# Sheet2.net
KiCad netlist of a schematic drawn in Altium Designer
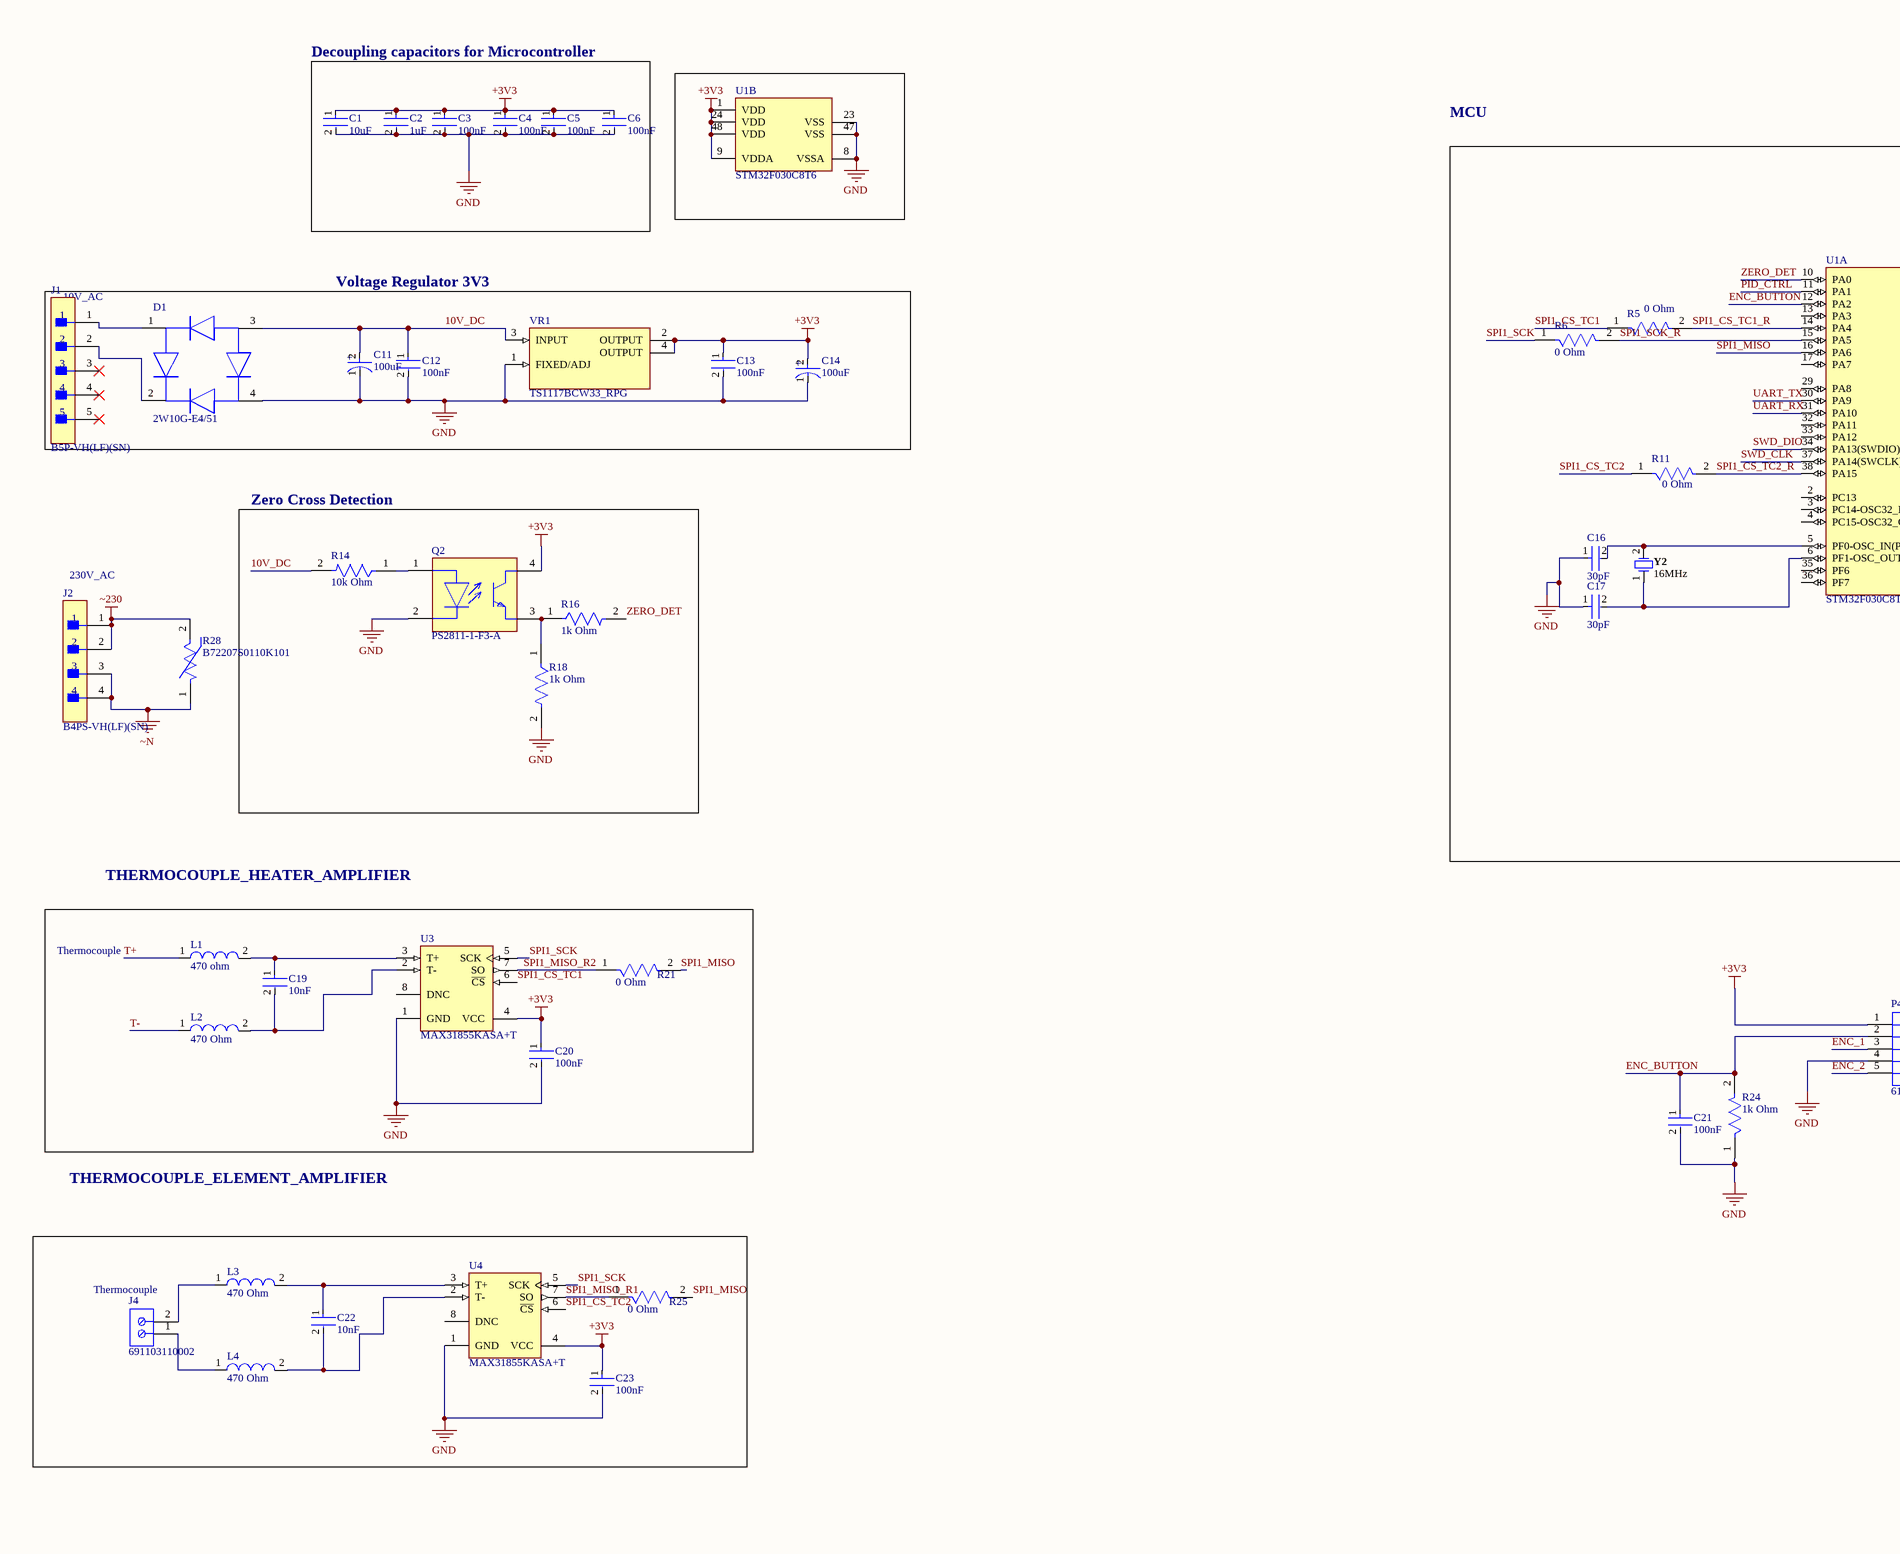
[diagram p0: Sheet2.SchDoc, left]
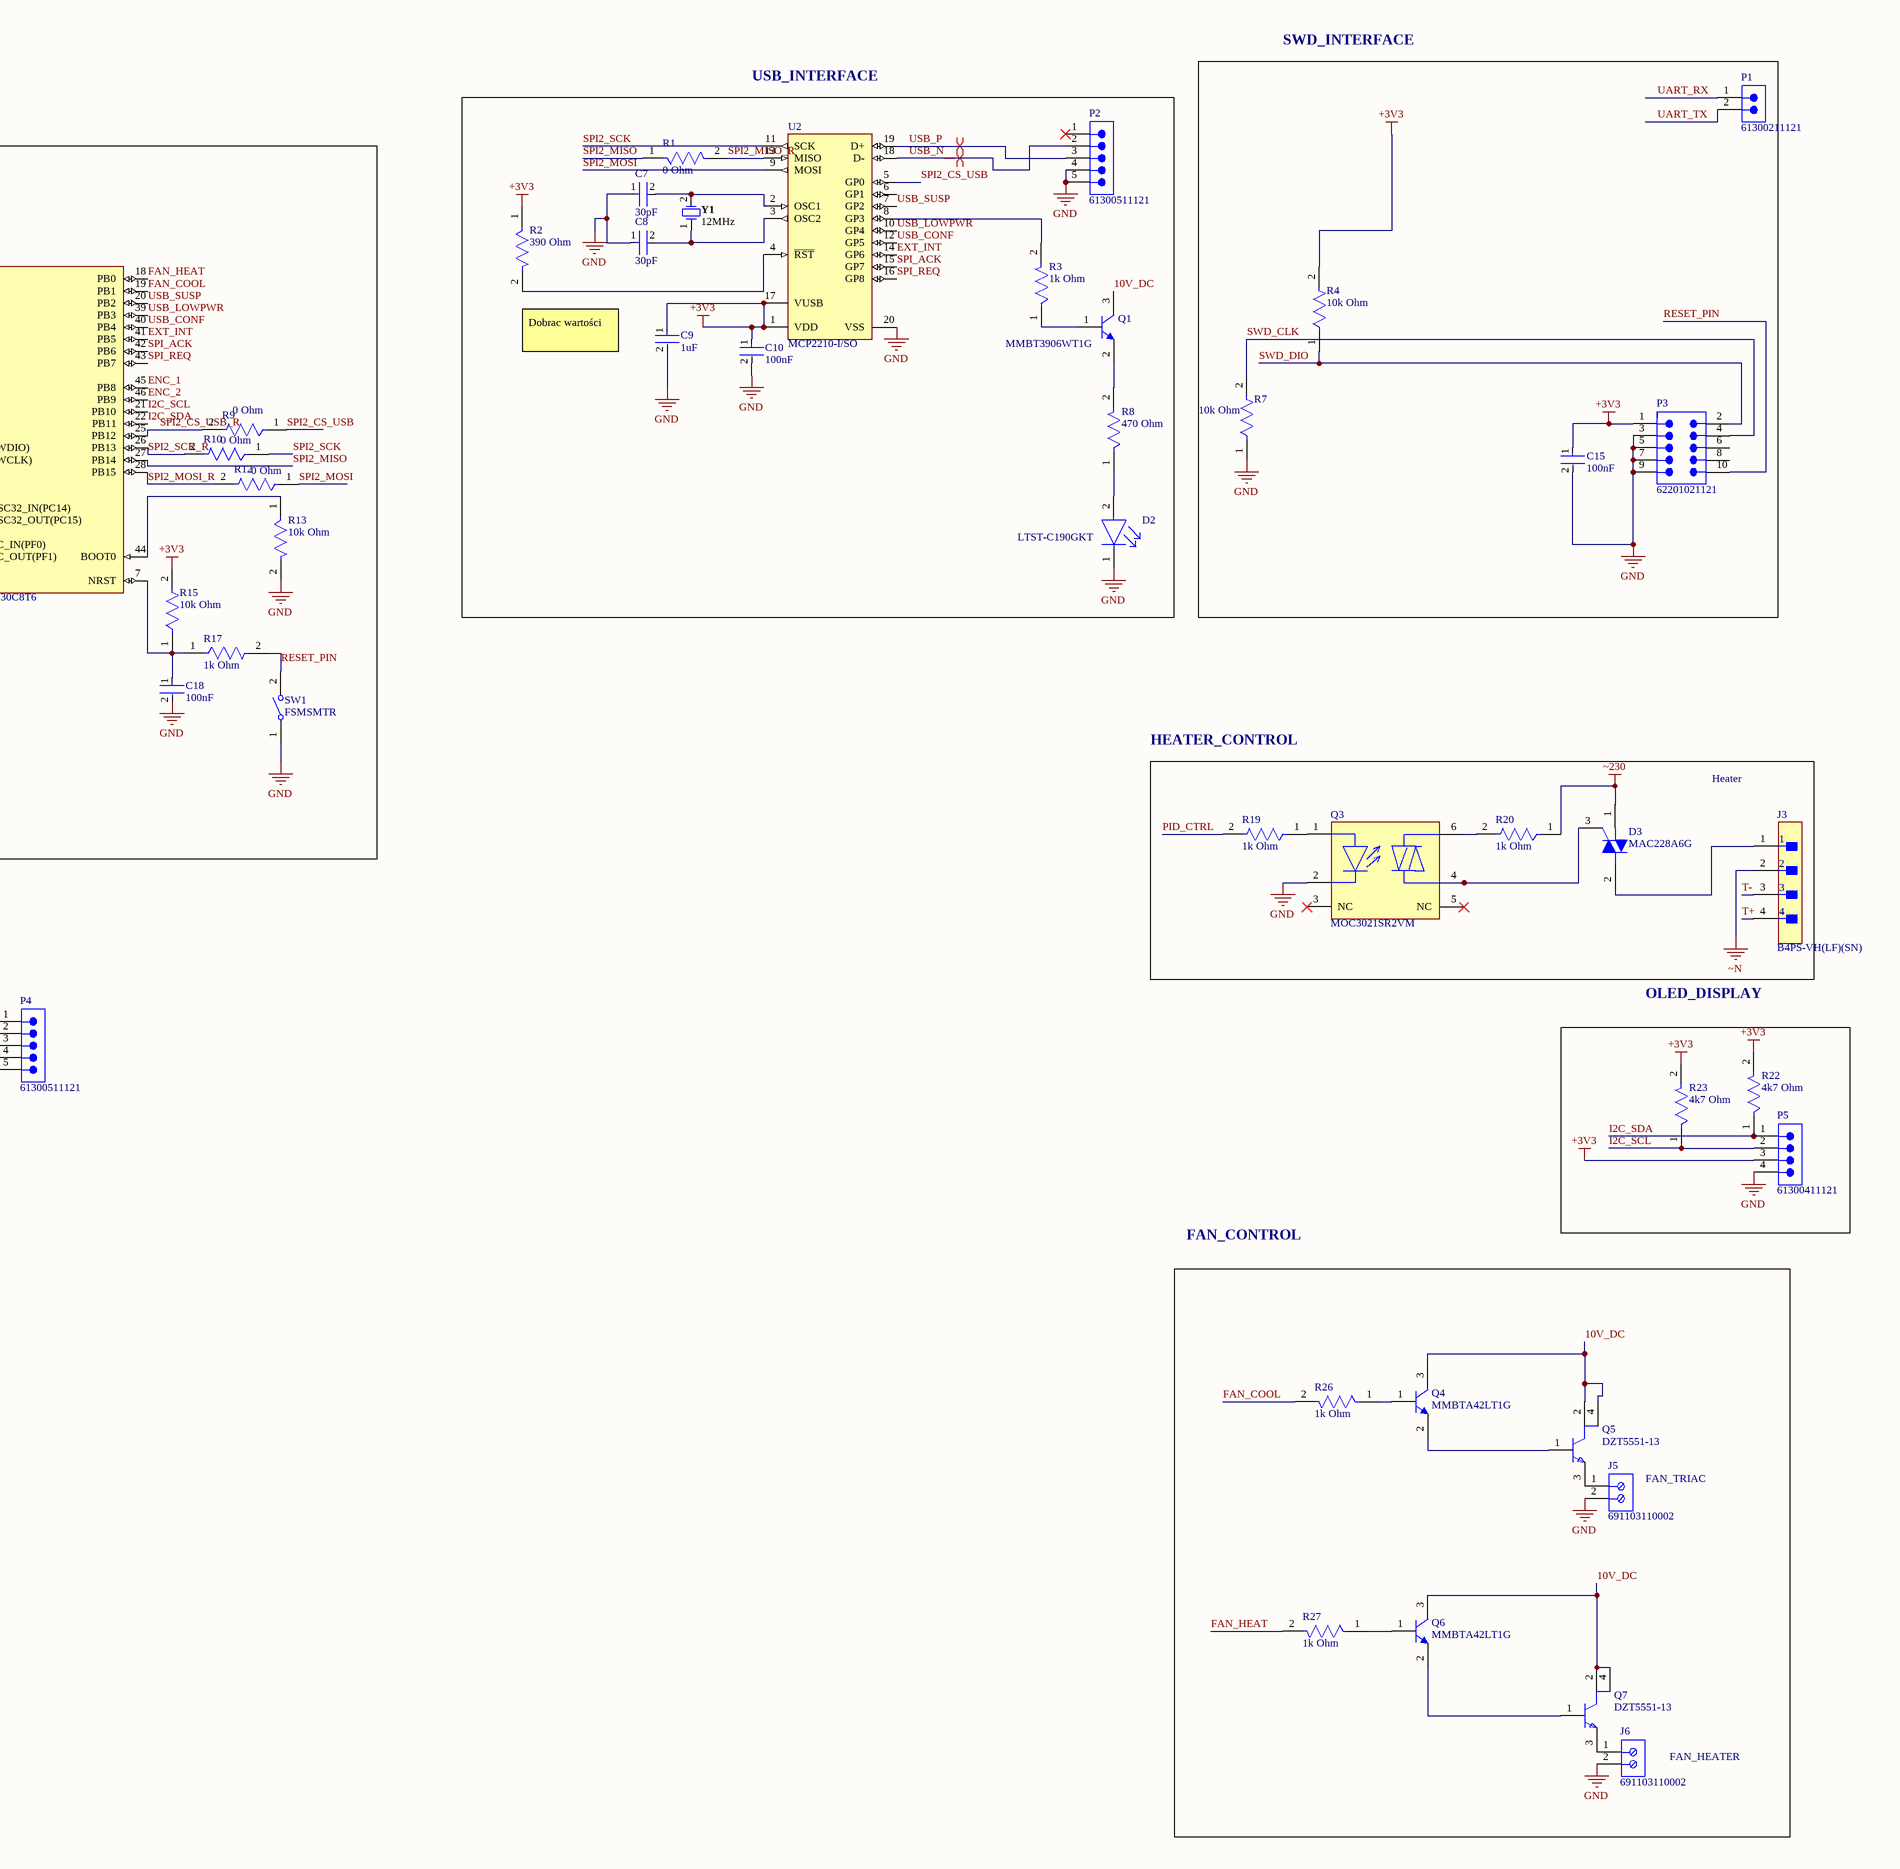
[diagram p1: Sheet2.SchDoc, right]

(export (version "E")
  (design (tool "Eeschema 10.0.6"))
  (components
    (comp (ref "C1")
      (value "10uF")
      (footprint "FP-CC0805-0_85-MFG")
      (description "CAP CER 0.1UF 50V X7R 0805")
      (fields (field (name "TOLERANCE") "0.1") (field (name "MANUFACTURER PART NUMBER") "CC0805KRX7R9BB104"))
      (libsource (lib "Altium Content Vault") (part "11868f565c42a9108669ba33697ecf6"))
    )
    (comp (ref "C2")
      (value "1uF")
      (footprint "FP-CC0805-0_85-MFG")
      (description "CAP CER 0.1UF 50V X7R 0805")
      (fields (field (name "TOLERANCE") "0.1") (field (name "MANUFACTURER PART NUMBER") "CC0805KRX7R9BB104"))
      (libsource (lib "Altium Content Vault") (part "11868f565c42a9108669ba33697ecf6"))
    )
    (comp (ref "C3")
      (value "100nF")
      (footprint "FP-CC0805-0_85-MFG")
      (description "CAP CER 0.1UF 50V X7R 0805")
      (fields (field (name "TOLERANCE") "0.1") (field (name "MANUFACTURER PART NUMBER") "CC0805KRX7R9BB104"))
      (libsource (lib "Altium Content Vault") (part "11868f565c42a9108669ba33697ecf6"))
    )
    (comp (ref "C4")
      (value "100nF")
      (footprint "FP-CC0805-0_85-MFG")
      (description "CAP CER 0.1UF 50V X7R 0805")
      (fields (field (name "TOLERANCE") "0.1") (field (name "MANUFACTURER PART NUMBER") "CC0805KRX7R9BB104"))
      (libsource (lib "Altium Content Vault") (part "11868f565c42a9108669ba33697ecf6"))
    )
    (comp (ref "C5")
      (value "100nF")
      (footprint "FP-CC0805-0_85-MFG")
      (description "CAP CER 0.1UF 50V X7R 0805")
      (fields (field (name "TOLERANCE") "0.1") (field (name "MANUFACTURER PART NUMBER") "CC0805KRX7R9BB104"))
      (libsource (lib "Altium Content Vault") (part "11868f565c42a9108669ba33697ecf6"))
    )
    (comp (ref "C6")
      (value "100nF")
      (footprint "FP-CC0805-0_85-MFG")
      (description "CAP CER 0.1UF 50V X7R 0805")
      (fields (field (name "TOLERANCE") "0.1") (field (name "MANUFACTURER PART NUMBER") "CC0805KRX7R9BB104"))
      (libsource (lib "Altium Content Vault") (part "11868f565c42a9108669ba33697ecf6"))
    )
    (comp (ref "C7")
      (value "30pF")
      (footprint "FP-CC0805-0_85-MFG")
      (description "CAP CER 0.1UF 50V X7R 0805")
      (fields (field (name "TOLERANCE") "0.1") (field (name "MANUFACTURER PART NUMBER") "CC0805KRX7R9BB104"))
      (libsource (lib "Altium Content Vault") (part "11868f565c42a9108669ba33697ecf6"))
    )
    (comp (ref "C8")
      (value "30pF")
      (footprint "FP-CC0805-0_85-MFG")
      (description "CAP CER 0.1UF 50V X7R 0805")
      (fields (field (name "TOLERANCE") "0.1") (field (name "MANUFACTURER PART NUMBER") "CC0805KRX7R9BB104"))
      (libsource (lib "Altium Content Vault") (part "11868f565c42a9108669ba33697ecf6"))
    )
    (comp (ref "C9")
      (value "1uF")
      (footprint "FP-CC0805-0_85-MFG")
      (description "CAP CER 0.1UF 50V X7R 0805")
      (fields (field (name "TOLERANCE") "0.1") (field (name "MANUFACTURER PART NUMBER") "CC0805KRX7R9BB104"))
      (libsource (lib "Altium Content Vault") (part "11868f565c42a9108669ba33697ecf6"))
    )
    (comp (ref "C10")
      (value "100nF")
      (footprint "FP-CC0805-0_85-MFG")
      (description "CAP CER 0.1UF 50V X7R 0805")
      (fields (field (name "TOLERANCE") "0.1") (field (name "MANUFACTURER PART NUMBER") "CC0805KRX7R9BB104"))
      (libsource (lib "Altium Content Vault") (part "11868f565c42a9108669ba33697ecf6"))
    )
    (comp (ref "C11")
      (value "100uF")
      (footprint "FP-RAD-TH-D_10_0_5-L_12_5-MFG")
      (description "Aluminum Electrolytic Capacitors (Radial Lead Type) 3.3uF ±20% 400V")
      (fields (field (name "TOLERANCE") "20%") (field (name "VOLTAGE") "400V"))
      (libsource (lib "Altium Content Vault") (part "203bc49f2ac43e59fd269a8c329ed05"))
    )
    (comp (ref "C12")
      (value "100nF")
      (footprint "FP-CC0805-0_85-MFG")
      (description "CAP CER 0.1UF 50V X7R 0805")
      (fields (field (name "TOLERANCE") "0.1") (field (name "MANUFACTURER PART NUMBER") "CC0805KRX7R9BB104"))
      (libsource (lib "Altium Content Vault") (part "11868f565c42a9108669ba33697ecf6"))
    )
    (comp (ref "C13")
      (value "100nF")
      (footprint "FP-CC0805-0_85-MFG")
      (description "CAP CER 0.1UF 50V X7R 0805")
      (fields (field (name "TOLERANCE") "0.1") (field (name "MANUFACTURER PART NUMBER") "CC0805KRX7R9BB104"))
      (libsource (lib "Altium Content Vault") (part "11868f565c42a9108669ba33697ecf6"))
    )
    (comp (ref "C14")
      (value "100uF")
      (footprint "FP-RAD-TH-D_10_0_5-L_12_5-MFG")
      (description "Aluminum Electrolytic Capacitors (Radial Lead Type) 3.3uF ±20% 400V")
      (fields (field (name "TOLERANCE") "20%") (field (name "VOLTAGE") "400V"))
      (libsource (lib "Altium Content Vault") (part "203bc49f2ac43e59fd269a8c329ed05"))
    )
    (comp (ref "C15")
      (value "100nF")
      (footprint "FP-CC0805-0_85-MFG")
      (description "CAP CER 0.1UF 50V X7R 0805")
      (fields (field (name "TOLERANCE") "0.1") (field (name "MANUFACTURER PART NUMBER") "CC0805KRX7R9BB104"))
      (libsource (lib "Altium Content Vault") (part "11868f565c42a9108669ba33697ecf6"))
    )
    (comp (ref "C16")
      (value "30pF")
      (footprint "FP-CC0805-0_85-MFG")
      (description "CAP CER 0.1UF 50V X7R 0805")
      (fields (field (name "TOLERANCE") "0.1") (field (name "MANUFACTURER PART NUMBER") "CC0805KRX7R9BB104"))
      (libsource (lib "Altium Content Vault") (part "11868f565c42a9108669ba33697ecf6"))
    )
    (comp (ref "C17")
      (value "30pF")
      (footprint "FP-CC0805-0_85-MFG")
      (description "CAP CER 0.1UF 50V X7R 0805")
      (fields (field (name "TOLERANCE") "0.1") (field (name "MANUFACTURER PART NUMBER") "CC0805KRX7R9BB104"))
      (libsource (lib "Altium Content Vault") (part "11868f565c42a9108669ba33697ecf6"))
    )
    (comp (ref "C18")
      (value "100nF")
      (footprint "FP-CC0805-0_85-MFG")
      (description "CAP CER 0.1UF 50V X7R 0805")
      (fields (field (name "TOLERANCE") "0.1") (field (name "MANUFACTURER PART NUMBER") "CC0805KRX7R9BB104"))
      (libsource (lib "Altium Content Vault") (part "11868f565c42a9108669ba33697ecf6"))
    )
    (comp (ref "C19")
      (value "10nF")
      (footprint "FP-CC0805-0_85-MFG")
      (description "CAP CER 0.1UF 50V X7R 0805")
      (fields (field (name "TOLERANCE") "0.1") (field (name "MANUFACTURER PART NUMBER") "CC0805KRX7R9BB104"))
      (libsource (lib "Altium Content Vault") (part "11868f565c42a9108669ba33697ecf6"))
    )
    (comp (ref "C20")
      (value "100nF")
      (footprint "FP-CC0805-0_85-MFG")
      (description "CAP CER 0.1UF 50V X7R 0805")
      (fields (field (name "TOLERANCE") "0.1") (field (name "MANUFACTURER PART NUMBER") "CC0805KRX7R9BB104"))
      (libsource (lib "Altium Content Vault") (part "11868f565c42a9108669ba33697ecf6"))
    )
    (comp (ref "C21")
      (value "100nF")
      (footprint "FP-CC0805-0_85-MFG")
      (description "CAP CER 0.1UF 50V X7R 0805")
      (fields (field (name "TOLERANCE") "0.1") (field (name "MANUFACTURER PART NUMBER") "CC0805KRX7R9BB104"))
      (libsource (lib "Altium Content Vault") (part "11868f565c42a9108669ba33697ecf6"))
    )
    (comp (ref "C22")
      (value "10nF")
      (footprint "FP-CC0805-0_85-MFG")
      (description "CAP CER 0.1UF 50V X7R 0805")
      (fields (field (name "TOLERANCE") "0.1") (field (name "MANUFACTURER PART NUMBER") "CC0805KRX7R9BB104"))
      (libsource (lib "Altium Content Vault") (part "11868f565c42a9108669ba33697ecf6"))
    )
    (comp (ref "C23")
      (value "100nF")
      (footprint "FP-CC0805-0_85-MFG")
      (description "CAP CER 0.1UF 50V X7R 0805")
      (fields (field (name "TOLERANCE") "0.1") (field (name "MANUFACTURER PART NUMBER") "CC0805KRX7R9BB104"))
      (libsource (lib "Altium Content Vault") (part "11868f565c42a9108669ba33697ecf6"))
    )
    (comp (ref "D1")
      (value "2W10G-E4/51")
      (footprint "FP-WOG-MFG")
      (description "BRIDGE RECT 1PHASE 1KV 2A WOG")
      (fields
        (field (name "MANUFACTURER") "Vishay")
        (field (name "OCTOPART") "https://octopart.com/2w10g-e4%2F51-vishay-42173035")
      )
      (libsource (lib "Altium Content Vault") (part "e2cd90391d24004f10f4733dacedb97"))
    )
    (comp (ref "D2")
      (value "LTST-C190GKT")
      (footprint "FP-LTST-C190GKT-MFG")
      (description "LED GREEN CLEAR CHIP SMD")
      (fields (field (name "VOLTAGE") "2V"))
      (libsource (lib "Altium Content Vault") (part "8706943c75ba83719d021d2fdc84c58"))
    )
    (comp (ref "D3")
      (value "MAC228A6G")
      (footprint "ONSC-TO-220-3-221A-09")
      (description "Sensitive Gate Triacs, Silicon Bidirectional Thyristor, 3-Pin TO-220, Pb-Free, Bulk Box")
      (fields (field (name "MANUFACTURER") "On Semiconductor"))
      (libsource (lib "Altium Content Vault") (part "ONSC-TRIAC-MT1MT2G-3"))
    )
    (comp (ref "J1")
      (value "B5P-VH(LF)(SN)")
      (footprint "FP-B5P-VH_LF_SN-MFG")
      (description "CONN HEADER VERT 5POS 3.96MM")
      (libsource (lib "Altium Content Vault") (part "051ac7c1f60a91215dd69c4e70fad1a"))
    )
    (comp (ref "J2")
      (value "B4PS-VH(LF)(SN)")
      (footprint "FP-B4PS-VH_LF_SN-MFG")
      (description "CONN HEADER R/A 4POS 3.96MM")
      (libsource (lib "") (part "299a8cea1bdcbc3624fe62c390fa72c_1"))
    )
    (comp (ref "J3")
      (value "B4PS-VH(LF)(SN)")
      (footprint "FP-B4PS-VH_LF_SN-MFG")
      (description "CONN HEADER R/A 4POS 3.96MM")
      (libsource (lib "Altium Content Vault") (part "299a8cea1bdcbc3624fe62c390fa72c"))
    )
    (comp (ref "J4")
      (value "691103110002")
      (footprint "691103110002")
      (fields (field (name "VOLTAGE") "125V"))
      (libsource (lib "Altium Content Vault") (part "TBL - 1R - 02P - Screw"))
    )
    (comp (ref "J5")
      (value "691103110002")
      (footprint "691103110002")
      (fields (field (name "VOLTAGE") "125V"))
      (libsource (lib "Altium Content Vault") (part "TBL - 1R - 02P - Screw"))
    )
    (comp (ref "J6")
      (value "691103110002")
      (footprint "691103110002")
      (fields (field (name "VOLTAGE") "125V"))
      (libsource (lib "Altium Content Vault") (part "TBL - 1R - 02P - Screw"))
    )
    (comp (ref "L1")
      (value "470 ohm")
      (footprint "SMD-0805")
      (description "SMD EMI Suppression Ferrite Bead WE-CBF, Z = 470 Ohm")
      (libsource (lib "Altium Content Vault") (part "PAS-IND-INDUCTOR-2"))
    )
    (comp (ref "L2")
      (value "470 Ohm")
      (footprint "SMD-0805")
      (description "SMD EMI Suppression Ferrite Bead WE-CBF, Z = 470 Ohm")
      (libsource (lib "Altium Content Vault") (part "PAS-IND-INDUCTOR-2"))
    )
    (comp (ref "L3")
      (value "470 Ohm")
      (footprint "SMD-0805")
      (description "SMD EMI Suppression Ferrite Bead WE-CBF, Z = 470 Ohm")
      (libsource (lib "Altium Content Vault") (part "PAS-IND-INDUCTOR-2"))
    )
    (comp (ref "L4")
      (value "470 Ohm")
      (footprint "SMD-0805")
      (description "SMD EMI Suppression Ferrite Bead WE-CBF, Z = 470 Ohm")
      (libsource (lib "Altium Content Vault") (part "PAS-IND-INDUCTOR-2"))
    )
    (comp (ref "P1")
      (value "61300211121")
      (footprint "61300211121")
      (libsource (lib "Altium Content Vault") (part "Header_Male_1R_02P"))
    )
    (comp (ref "P2")
      (value "61300511121")
      (footprint "61300511121")
      (libsource (lib "Altium Content Vault") (part "Header_Male_1R_05P"))
    )
    (comp (ref "P3")
      (value "62201021121")
      (footprint "62201021121")
      (libsource (lib "Altium Content Vault") (part "Header_Male_2R_10P"))
    )
    (comp (ref "P4")
      (value "61300511121")
      (footprint "61300511121")
      (libsource (lib "Altium Content Vault") (part "Header_Male_1R_05P"))
    )
    (comp (ref "P5")
      (value "61300411121")
      (footprint "61300411121")
      (libsource (lib "Altium Content Vault") (part "Header_Male_1R_04P"))
    )
    (comp (ref "Q1")
      (value "MMBT3906WT1G")
      (footprint "ONSC-SC-70-3-419-04_V")
      (description "General Purpose Transistor, PNP Silicon, 3-Pin SC70, Pb-Free, Tape and Reel")
      (fields (field (name "MANUFACTURER") "On Semiconductor"))
      (libsource (lib "Altium Content Vault") (part "ONSC-NPN-B1E2C3-3"))
    )
    (comp (ref "Q2")
      (value "PS2811-1-F3-A")
      (footprint "SOP127P700X210_HS-5_SO4-Opto2_N")
      (description "Optocoupler DC-IN 1-CH Transistor DC-OUT 4-Pin SSOP Embossed T/R")
      (libsource (lib "Altium Content Vault") (part "f4732c5a005c16655bf03302f8bd1cc"))
    )
    (comp (ref "Q3")
      (value "MOC3021SR2VM")
      (footprint "FP-646BY-MFG")
      (description "MOC3021SR2VM Triac Driver Output Optocoupler, 6-Pin DIP 400V Random Phase")
      (libsource (lib "Altium Content Vault") (part "315d33d7a3de83856d3bd334bf87c2f"))
    )
    (comp (ref "Q4")
      (value "MMBTA42LT1G")
      (footprint "ONSC-SOT-23-3-318-08_V")
      (description "High Voltage Transistor, NPN Silicon, 3-Pin SOT-23, Pb-Free, Tape and Reel")
      (fields (field (name "MANUFACTURER") "On Semiconductor"))
      (libsource (lib "Altium Content Vault") (part "ONSC-NPN-B1E2C3-3"))
    )
    (comp (ref "Q5")
      (value "DZT5551-13")
      (footprint "FP-SOT223-MFG")
      (description "TRANS NPN 160V 0.6A SOT-223")
      (fields
        (field (name "MANUFACTURER") "Diodes")
        (field (name "OCTOPART") "https://octopart.com/dzt5551-13-diodes+inc.-12426785")
      )
      (libsource (lib "Altium Content Vault") (part "ef0222921274e2dfe3c88fb5f98777d"))
    )
    (comp (ref "Q6")
      (value "MMBTA42LT1G")
      (footprint "ONSC-SOT-23-3-318-08_V")
      (description "High Voltage Transistor, NPN Silicon, 3-Pin SOT-23, Pb-Free, Tape and Reel")
      (fields (field (name "MANUFACTURER") "On Semiconductor"))
      (libsource (lib "Altium Content Vault") (part "ONSC-NPN-B1E2C3-3"))
    )
    (comp (ref "Q7")
      (value "DZT5551-13")
      (footprint "FP-SOT223-MFG")
      (description "TRANS NPN 160V 0.6A SOT-223")
      (fields
        (field (name "MANUFACTURER") "Diodes")
        (field (name "OCTOPART") "https://octopart.com/dzt5551-13-diodes+inc.-12426785")
      )
      (libsource (lib "Altium Content Vault") (part "ef0222921274e2dfe3c88fb5f98777d"))
    )
    (comp (ref "R1")
      (value "0 Ohm")
      (footprint "FP-RMCF0805-MFG")
      (description "RES 0 OHM JUMPER 1/8W 0805")
      (libsource (lib "Altium Content Vault") (part "1029c3af85768c4190bb7ad29bc67b5"))
    )
    (comp (ref "R2")
      (value "390 Ohm")
      (footprint "FP-RMCF0805-MFG")
      (description "RES 0 OHM JUMPER 1/8W 0805")
      (libsource (lib "Altium Content Vault") (part "1029c3af85768c4190bb7ad29bc67b5"))
    )
    (comp (ref "R3")
      (value "1k Ohm")
      (footprint "FP-RMCF0805-MFG")
      (description "RES 0 OHM JUMPER 1/8W 0805")
      (libsource (lib "Altium Content Vault") (part "1029c3af85768c4190bb7ad29bc67b5"))
    )
    (comp (ref "R4")
      (value "10k Ohm")
      (footprint "FP-RMCF0805-MFG")
      (description "RES 0 OHM JUMPER 1/8W 0805")
      (libsource (lib "Altium Content Vault") (part "1029c3af85768c4190bb7ad29bc67b5"))
    )
    (comp (ref "R5")
      (value "0 Ohm")
      (footprint "FP-RMCF0805-MFG")
      (description "RES 0 OHM JUMPER 1/8W 0805")
      (libsource (lib "Altium Content Vault") (part "1029c3af85768c4190bb7ad29bc67b5"))
    )
    (comp (ref "R6")
      (value "0 Ohm")
      (footprint "FP-RMCF0805-MFG")
      (description "RES 0 OHM JUMPER 1/8W 0805")
      (libsource (lib "Altium Content Vault") (part "1029c3af85768c4190bb7ad29bc67b5"))
    )
    (comp (ref "R7")
      (value "10k Ohm")
      (footprint "FP-RMCF0805-MFG")
      (description "RES 0 OHM JUMPER 1/8W 0805")
      (libsource (lib "Altium Content Vault") (part "1029c3af85768c4190bb7ad29bc67b5"))
    )
    (comp (ref "R8")
      (value "470 Ohm")
      (footprint "FP-RMCF0805-MFG")
      (description "RES 0 OHM JUMPER 1/8W 0805")
      (libsource (lib "Altium Content Vault") (part "1029c3af85768c4190bb7ad29bc67b5"))
    )
    (comp (ref "R9")
      (value "0 Ohm")
      (footprint "FP-RMCF0805-MFG")
      (description "RES 0 OHM JUMPER 1/8W 0805")
      (libsource (lib "Altium Content Vault") (part "1029c3af85768c4190bb7ad29bc67b5"))
    )
    (comp (ref "R10")
      (value "0 Ohm")
      (footprint "FP-RMCF0805-MFG")
      (description "RES 0 OHM JUMPER 1/8W 0805")
      (libsource (lib "Altium Content Vault") (part "1029c3af85768c4190bb7ad29bc67b5"))
    )
    (comp (ref "R11")
      (value "0 Ohm")
      (footprint "FP-RMCF0805-MFG")
      (description "RES 0 OHM JUMPER 1/8W 0805")
      (libsource (lib "Altium Content Vault") (part "1029c3af85768c4190bb7ad29bc67b5"))
    )
    (comp (ref "R12")
      (value "0 Ohm")
      (footprint "FP-RMCF0805-MFG")
      (description "RES 0 OHM JUMPER 1/8W 0805")
      (libsource (lib "Altium Content Vault") (part "1029c3af85768c4190bb7ad29bc67b5"))
    )
    (comp (ref "R13")
      (value "10k Ohm")
      (footprint "FP-RMCF0805-MFG")
      (description "RES 0 OHM JUMPER 1/8W 0805")
      (libsource (lib "Altium Content Vault") (part "1029c3af85768c4190bb7ad29bc67b5"))
    )
    (comp (ref "R14")
      (value "10k Ohm")
      (footprint "FP-RMCF0805-MFG")
      (description "RES 0 OHM JUMPER 1/8W 0805")
      (libsource (lib "Altium Content Vault") (part "1029c3af85768c4190bb7ad29bc67b5"))
    )
    (comp (ref "R15")
      (value "10k Ohm")
      (footprint "FP-RMCF0805-MFG")
      (description "RES 0 OHM JUMPER 1/8W 0805")
      (libsource (lib "Altium Content Vault") (part "1029c3af85768c4190bb7ad29bc67b5"))
    )
    (comp (ref "R16")
      (value "1k Ohm")
      (footprint "FP-RMCF0805-MFG")
      (description "RES 0 OHM JUMPER 1/8W 0805")
      (libsource (lib "Altium Content Vault") (part "1029c3af85768c4190bb7ad29bc67b5"))
    )
    (comp (ref "R17")
      (value "1k Ohm")
      (footprint "FP-RMCF0805-MFG")
      (description "RES 0 OHM JUMPER 1/8W 0805")
      (libsource (lib "Altium Content Vault") (part "1029c3af85768c4190bb7ad29bc67b5"))
    )
    (comp (ref "R18")
      (value "1k Ohm")
      (footprint "FP-RMCF0805-MFG")
      (description "RES 0 OHM JUMPER 1/8W 0805")
      (libsource (lib "Altium Content Vault") (part "1029c3af85768c4190bb7ad29bc67b5"))
    )
    (comp (ref "R19")
      (value "1k Ohm")
      (footprint "FP-RMCF0805-MFG")
      (description "RES 0 OHM JUMPER 1/8W 0805")
      (libsource (lib "Altium Content Vault") (part "1029c3af85768c4190bb7ad29bc67b5"))
    )
    (comp (ref "R20")
      (value "1k Ohm")
      (footprint "FP-RMCF0805-MFG")
      (description "RES 0 OHM JUMPER 1/8W 0805")
      (libsource (lib "Altium Content Vault") (part "1029c3af85768c4190bb7ad29bc67b5"))
    )
    (comp (ref "R21")
      (value "0 Ohm")
      (footprint "FP-RMCF0805-MFG")
      (description "RES 0 OHM JUMPER 1/8W 0805")
      (libsource (lib "Altium Content Vault") (part "1029c3af85768c4190bb7ad29bc67b5"))
    )
    (comp (ref "R22")
      (value "4k7 Ohm")
      (footprint "FP-RMCF0805-MFG")
      (description "RES 0 OHM JUMPER 1/8W 0805")
      (libsource (lib "Altium Content Vault") (part "1029c3af85768c4190bb7ad29bc67b5"))
    )
    (comp (ref "R23")
      (value "4k7 Ohm")
      (footprint "FP-RMCF0805-MFG")
      (description "RES 0 OHM JUMPER 1/8W 0805")
      (libsource (lib "Altium Content Vault") (part "1029c3af85768c4190bb7ad29bc67b5"))
    )
    (comp (ref "R24")
      (value "1k Ohm")
      (footprint "FP-RMCF0805-MFG")
      (description "RES 0 OHM JUMPER 1/8W 0805")
      (libsource (lib "Altium Content Vault") (part "1029c3af85768c4190bb7ad29bc67b5"))
    )
    (comp (ref "R25")
      (value "0 Ohm")
      (footprint "FP-RMCF0805-MFG")
      (description "RES 0 OHM JUMPER 1/8W 0805")
      (libsource (lib "Altium Content Vault") (part "1029c3af85768c4190bb7ad29bc67b5"))
    )
    (comp (ref "R26")
      (value "1k Ohm")
      (footprint "FP-RMCF0805-MFG")
      (description "RES 0 OHM JUMPER 1/8W 0805")
      (libsource (lib "Altium Content Vault") (part "1029c3af85768c4190bb7ad29bc67b5"))
    )
    (comp (ref "R27")
      (value "1k Ohm")
      (footprint "FP-RMCF0805-MFG")
      (description "RES 0 OHM JUMPER 1/8W 0805")
      (libsource (lib "Altium Content Vault") (part "1029c3af85768c4190bb7ad29bc67b5"))
    )
    (comp (ref "R28")
      (value "B72207S0110K101")
      (footprint "FP-B72207S0110K101-MFG")
      (description "18V 250A Varistor 1 Circuit Through Hole Disc 7mm")
      (fields (field (name "MANUFACTURER") "EPCOS"))
      (libsource (lib "Altium Content Vault") (part "78a88060d5b7b043d6e48adc4284376"))
    )
    (comp (ref "SW1")
      (value "FSMSMTR")
      (footprint "TECO-FSMSMTR_V")
      (description "FSMSM Push Button Switch, 50 mA, -35 to 85 degC, 2-Pin SMD, RoHS, Tape and Reel")
      (fields (field (name "MANUFACTURER") "TE Connectivity"))
      (libsource (lib "Altium Content Vault") (part "SW-SPST-2_C"))
    )
    (comp (ref "U1")
      (value "STM32F030C8T6")
      (footprint "STM-LQFP48_M")
      (libsource (lib "Altium Content Vault") (part "MC-ARM-STM32F030_X8-SQ48"))
    )
    (comp (ref "U2")
      (value "MCP2210-I/SO")
      (footprint "SOIC-SO20_N")
      (description "USB-to-SPI Protocol Converter with GPIO (Master Mode), 20-Pin SOIC, Industrial Temperature")
      (libsource (lib "Altium Content Vault") (part "COM-USB-MCP2210-20"))
    )
    (comp (ref "U3")
      (value "MAX31855KASA+T")
      (footprint "MAXM-S8+4_N")
      (fields (field (name "GENERIC PART NUMBER") "MAX31855"))
      (libsource (lib "Altium Content Vault") (part "MAX31855-S8+4"))
    )
    (comp (ref "U4")
      (value "MAX31855KASA+T")
      (footprint "MAXM-S8+4_N")
      (fields (field (name "GENERIC PART NUMBER") "MAX31855"))
      (libsource (lib "Altium Content Vault") (part "MAX31855-S8+4"))
    )
    (comp (ref "VR1")
      (value "TS1117BCW33_RPG")
      (footprint "VREG_TS1117BCW50_RPG")
      (fields (field (name "MP") "TS1117BCW50_RPG"))
      (libsource (lib "TS1117BCW50_RPG") (part "TS1117BCW50_RPG"))
    )
    (comp (ref "Y1")
      (value "12MHz")
      (footprint "FOX-FOXSLF160-20")
      (description "Resistance Weld Thru-Hole Crystal, 16 MHz, -20 to 70 degC, 2-Pin THD, RoHS, Bulk")
      (fields (field (name "TOLERANCE") "1%"))
      (libsource (lib "Altium Content Vault") (part "XTAL-1-2-2"))
    )
    (comp (ref "Y2")
      (value "16MHz")
      (footprint "FOX-FOXSLF160-20")
      (description "Resistance Weld Thru-Hole Crystal, 16 MHz, -20 to 70 degC, 2-Pin THD, RoHS, Bulk")
      (fields (field (name "TOLERANCE") "1%"))
      (libsource (lib "Altium Content Vault") (part "XTAL-1-2-2"))
    )
  )
  (nets
    (net (code "1") (name "+3V3") (class "Default")
      (node (ref "C1") (pin "1") (pinfunction "1_1") (pintype "passive"))
      (node (ref "C10") (pin "1") (pinfunction "1_1") (pintype "passive"))
      (node (ref "C13") (pin "1") (pinfunction "1_1") (pintype "passive"))
      (node (ref "C14") (pin "2") (pinfunction "A_2") (pintype "passive"))
      (node (ref "C15") (pin "1") (pinfunction "1_1") (pintype "passive"))
      (node (ref "C2") (pin "1") (pinfunction "1_1") (pintype "passive"))
      (node (ref "C20") (pin "1") (pinfunction "1_1") (pintype "passive"))
      (node (ref "C23") (pin "1") (pinfunction "1_1") (pintype "passive"))
      (node (ref "C3") (pin "1") (pinfunction "1_1") (pintype "passive"))
      (node (ref "C4") (pin "1") (pinfunction "1_1") (pintype "passive"))
      (node (ref "C5") (pin "1") (pinfunction "1_1") (pintype "passive"))
      (node (ref "C6") (pin "1") (pinfunction "1_1") (pintype "passive"))
      (node (ref "C9") (pin "1") (pinfunction "1_1") (pintype "passive"))
      (node (ref "P3") (pin "1") (pinfunction "1_1") (pintype "passive"))
      (node (ref "P4") (pin "1") (pinfunction "1_1") (pintype "passive"))
      (node (ref "P5") (pin "3") (pinfunction "3_3") (pintype "passive"))
      (node (ref "Q2") (pin "4") (pinfunction "C_4") (pintype "passive"))
      (node (ref "R15") (pin "2") (pinfunction "2_2") (pintype "passive"))
      (node (ref "R2") (pin "1") (pinfunction "1_1") (pintype "passive"))
      (node (ref "R22") (pin "2") (pinfunction "2_2") (pintype "passive"))
      (node (ref "R23") (pin "2") (pinfunction "2_2") (pintype "passive"))
      (node (ref "R4") (pin "2") (pinfunction "2_2") (pintype "passive"))
      (node (ref "U1") (pin "1") (pinfunction "VDD_1") (pintype "power_in"))
      (node (ref "U1") (pin "24") (pinfunction "VDD_24") (pintype "power_in"))
      (node (ref "U1") (pin "48") (pinfunction "VDD_48") (pintype "power_in"))
      (node (ref "U1") (pin "9") (pinfunction "VDDA_9") (pintype "power_in"))
      (node (ref "U2") (pin "1") (pinfunction "VDD_1") (pintype "power_in"))
      (node (ref "U2") (pin "17") (pinfunction "VUSB_17") (pintype "power_in"))
      (node (ref "U3") (pin "4") (pinfunction "VCC_4") (pintype "power_in"))
      (node (ref "U4") (pin "4") (pinfunction "VCC_4") (pintype "power_in"))
      (node (ref "VR1") (pin "2") (pinfunction "OUTPUT_2") (pintype "power_in"))
      (node (ref "VR1") (pin "4") (pinfunction "OUTPUT_4") (pintype "power_in"))
    )
    (net (code "2") (name "/10V_DC") (class "Default")
      (node (ref "C11") (pin "2") (pinfunction "A_2") (pintype "passive"))
      (node (ref "C12") (pin "1") (pinfunction "1_1") (pintype "passive"))
      (node (ref "D1") (pin "3") (pinfunction "-_3") (pintype "passive"))
      (node (ref "Q1") (pin "3") (pinfunction "C_3") (pintype "passive"))
      (node (ref "Q4") (pin "3") (pinfunction "C_3") (pintype "passive"))
      (node (ref "Q5") (pin "2") (pinfunction "C_2") (pintype "passive"))
      (node (ref "Q5") (pin "4") (pinfunction "C_4") (pintype "passive"))
      (node (ref "Q6") (pin "3") (pinfunction "C_3") (pintype "passive"))
      (node (ref "Q7") (pin "2") (pinfunction "C_2") (pintype "passive"))
      (node (ref "Q7") (pin "4") (pinfunction "C_4") (pintype "passive"))
      (node (ref "R14") (pin "2") (pinfunction "2_2") (pintype "passive"))
      (node (ref "VR1") (pin "3") (pinfunction "INPUT_3") (pintype "input"))
    )
    (net (code "3") (name "/ENC_1") (class "Default")
      (node (ref "P4") (pin "3") (pinfunction "3_3") (pintype "passive"))
      (node (ref "U1") (pin "45") (pinfunction "PB8_45") (pintype "bidirectional"))
    )
    (net (code "4") (name "/ENC_2") (class "Default")
      (node (ref "P4") (pin "5") (pinfunction "5_5") (pintype "passive"))
      (node (ref "U1") (pin "46") (pinfunction "PB9_46") (pintype "bidirectional"))
    )
    (net (code "5") (name "/ENC_BUTTON") (class "Default")
      (node (ref "C21") (pin "1") (pinfunction "1_1") (pintype "passive"))
      (node (ref "P4") (pin "2") (pinfunction "2_2") (pintype "passive"))
      (node (ref "R24") (pin "2") (pinfunction "2_2") (pintype "passive"))
      (node (ref "U1") (pin "12") (pinfunction "PA2_12") (pintype "bidirectional"))
    )
    (net (code "6") (name "/EXT_INT") (class "Default")
      (node (ref "U1") (pin "41") (pinfunction "PB5_41") (pintype "bidirectional"))
      (node (ref "U2") (pin "14") (pinfunction "GP6_14") (pintype "bidirectional"))
    )
    (net (code "7") (name "/FAN_COOL") (class "Default")
      (node (ref "R26") (pin "2") (pinfunction "2_2") (pintype "passive"))
      (node (ref "U1") (pin "19") (pinfunction "PB1_19") (pintype "bidirectional"))
    )
    (net (code "8") (name "/FAN_HEAT") (class "Default")
      (node (ref "R27") (pin "2") (pinfunction "2_2") (pintype "passive"))
      (node (ref "U1") (pin "18") (pinfunction "PB0_18") (pintype "bidirectional"))
    )
    (net (code "9") (name "/I2C_SCL") (class "Default")
      (node (ref "P5") (pin "2") (pinfunction "2_2") (pintype "passive"))
      (node (ref "R23") (pin "1") (pinfunction "1_1") (pintype "passive"))
      (node (ref "U1") (pin "21") (pinfunction "PB10_21") (pintype "bidirectional"))
    )
    (net (code "10") (name "/I2C_SDA") (class "Default")
      (node (ref "P5") (pin "1") (pinfunction "1_1") (pintype "passive"))
      (node (ref "R22") (pin "1") (pinfunction "1_1") (pintype "passive"))
      (node (ref "U1") (pin "22") (pinfunction "PB11_22") (pintype "bidirectional"))
    )
    (net (code "11") (name "/PID_CTRL") (class "Default")
      (node (ref "R19") (pin "2") (pinfunction "2_2") (pintype "passive"))
      (node (ref "U1") (pin "11") (pinfunction "PA1_11") (pintype "bidirectional"))
    )
    (net (code "12") (name "/RESET_PIN") (class "Default")
      (node (ref "P3") (pin "10") (pinfunction "10_10") (pintype "passive"))
      (node (ref "R17") (pin "2") (pinfunction "2_2") (pintype "passive"))
      (node (ref "SW1") (pin "2") (pinfunction "2_2") (pintype "passive"))
    )
    (net (code "13") (name "/SPI1_CS_TC1") (class "Default")
      (node (ref "R5") (pin "1") (pinfunction "1_1") (pintype "passive"))
      (node (ref "U3") (pin "6") (pinfunction "~{CS}_6") (pintype "input"))
    )
    (net (code "14") (name "/SPI1_CS_TC1_R") (class "Default")
      (node (ref "R5") (pin "2") (pinfunction "2_2") (pintype "passive"))
      (node (ref "U1") (pin "14") (pinfunction "PA4_14") (pintype "bidirectional"))
    )
    (net (code "15") (name "/SPI1_CS_TC2") (class "Default")
      (node (ref "R11") (pin "1") (pinfunction "1_1") (pintype "passive"))
      (node (ref "U4") (pin "6") (pinfunction "~{CS}_6") (pintype "input"))
    )
    (net (code "16") (name "/SPI1_CS_TC2_R") (class "Default")
      (node (ref "R11") (pin "2") (pinfunction "2_2") (pintype "passive"))
      (node (ref "U1") (pin "38") (pinfunction "PA15_38") (pintype "bidirectional"))
    )
    (net (code "17") (name "/SPI1_MISO") (class "Default")
      (node (ref "R21") (pin "2") (pinfunction "2_2") (pintype "passive"))
      (node (ref "R25") (pin "2") (pinfunction "2_2") (pintype "passive"))
      (node (ref "U1") (pin "16") (pinfunction "PA6_16") (pintype "bidirectional"))
    )
    (net (code "18") (name "/SPI1_MISO_R1") (class "Default")
      (node (ref "R25") (pin "1") (pinfunction "1_1") (pintype "passive"))
      (node (ref "U4") (pin "7") (pinfunction "SO_7") (pintype "output"))
    )
    (net (code "19") (name "/SPI1_MISO_R2") (class "Default")
      (node (ref "R21") (pin "1") (pinfunction "1_1") (pintype "passive"))
      (node (ref "U3") (pin "7") (pinfunction "SO_7") (pintype "output"))
    )
    (net (code "20") (name "/SPI1_SCK") (class "Default")
      (node (ref "R6") (pin "1") (pinfunction "1_1") (pintype "passive"))
      (node (ref "U3") (pin "5") (pinfunction "SCK_5") (pintype "input"))
      (node (ref "U4") (pin "5") (pinfunction "SCK_5") (pintype "input"))
    )
    (net (code "21") (name "/SPI1_SCK_R") (class "Default")
      (node (ref "R6") (pin "2") (pinfunction "2_2") (pintype "passive"))
      (node (ref "U1") (pin "15") (pinfunction "PA5_15") (pintype "bidirectional"))
    )
    (net (code "22") (name "/SPI2_CS_USB") (class "Default")
      (node (ref "R9") (pin "1") (pinfunction "1_1") (pintype "passive"))
      (node (ref "U2") (pin "5") (pinfunction "GP0_5") (pintype "bidirectional"))
    )
    (net (code "23") (name "/SPI2_CS_USB_R") (class "Default")
      (node (ref "R9") (pin "2") (pinfunction "2_2") (pintype "passive"))
      (node (ref "U1") (pin "25") (pinfunction "PB12_25") (pintype "bidirectional"))
    )
    (net (code "24") (name "/SPI2_MISO") (class "Default")
      (node (ref "R1") (pin "1") (pinfunction "1_1") (pintype "passive"))
      (node (ref "U1") (pin "27") (pinfunction "PB14_27") (pintype "bidirectional"))
    )
    (net (code "25") (name "/SPI2_MISO_R") (class "Default")
      (node (ref "R1") (pin "2") (pinfunction "2_2") (pintype "passive"))
      (node (ref "U2") (pin "13") (pinfunction "MISO_13") (pintype "input"))
    )
    (net (code "26") (name "/SPI2_MOSI") (class "Default")
      (node (ref "R12") (pin "1") (pinfunction "1_1") (pintype "passive"))
      (node (ref "U2") (pin "9") (pinfunction "MOSI_9") (pintype "output"))
    )
    (net (code "27") (name "/SPI2_MOSI_R") (class "Default")
      (node (ref "R12") (pin "2") (pinfunction "2_2") (pintype "passive"))
      (node (ref "U1") (pin "28") (pinfunction "PB15_28") (pintype "bidirectional"))
    )
    (net (code "28") (name "/SPI2_SCK") (class "Default")
      (node (ref "R10") (pin "1") (pinfunction "1_1") (pintype "passive"))
      (node (ref "U2") (pin "11") (pinfunction "SCK_11") (pintype "output"))
    )
    (net (code "29") (name "/SPI2_SCK_R") (class "Default")
      (node (ref "R10") (pin "2") (pinfunction "2_2") (pintype "passive"))
      (node (ref "U1") (pin "26") (pinfunction "PB13_26") (pintype "bidirectional"))
    )
    (net (code "30") (name "/SPI_ACK") (class "Default")
      (node (ref "U1") (pin "42") (pinfunction "PB6_42") (pintype "bidirectional"))
      (node (ref "U2") (pin "15") (pinfunction "GP7_15") (pintype "bidirectional"))
    )
    (net (code "31") (name "/SPI_REQ") (class "Default")
      (node (ref "U1") (pin "43") (pinfunction "PB7_43") (pintype "bidirectional"))
      (node (ref "U2") (pin "16") (pinfunction "GP8_16") (pintype "bidirectional"))
    )
    (net (code "32") (name "/SWD_CLK") (class "Default")
      (node (ref "P3") (pin "4") (pinfunction "4_4") (pintype "passive"))
      (node (ref "R7") (pin "2") (pinfunction "2_2") (pintype "passive"))
      (node (ref "U1") (pin "37") (pinfunction "PA14(SWCLK)_37") (pintype "bidirectional"))
    )
    (net (code "33") (name "/SWD_DIO") (class "Default")
      (node (ref "P3") (pin "2") (pinfunction "2_2") (pintype "passive"))
      (node (ref "R4") (pin "1") (pinfunction "1_1") (pintype "passive"))
      (node (ref "U1") (pin "34") (pinfunction "PA13(SWDIO)_34") (pintype "bidirectional"))
    )
    (net (code "34") (name "/T+") (class "Default")
      (node (ref "J3") (pin "4") (pinfunction "4_4") (pintype "passive"))
      (node (ref "L1") (pin "1") (pinfunction "1_1") (pintype "passive"))
    )
    (net (code "35") (name "/T-") (class "Default")
      (node (ref "J3") (pin "3") (pinfunction "3_3") (pintype "passive"))
      (node (ref "L2") (pin "1") (pinfunction "1_1") (pintype "passive"))
    )
    (net (code "36") (name "/UART_RX") (class "Default")
      (node (ref "P1") (pin "1") (pinfunction "1_1") (pintype "passive"))
      (node (ref "U1") (pin "31") (pinfunction "PA10_31") (pintype "bidirectional"))
    )
    (net (code "37") (name "/UART_TX") (class "Default")
      (node (ref "P1") (pin "2") (pinfunction "2_2") (pintype "passive"))
      (node (ref "U1") (pin "30") (pinfunction "PA9_30") (pintype "bidirectional"))
    )
    (net (code "38") (name "/USB_CONF") (class "Default")
      (node (ref "U1") (pin "40") (pinfunction "PB4_40") (pintype "bidirectional"))
      (node (ref "U2") (pin "12") (pinfunction "GP5_12") (pintype "bidirectional"))
    )
    (net (code "39") (name "/USB_LOWPWR") (class "Default")
      (node (ref "U1") (pin "39") (pinfunction "PB3_39") (pintype "bidirectional"))
      (node (ref "U2") (pin "10") (pinfunction "GP4_10") (pintype "bidirectional"))
    )
    (net (code "40") (name "/USB_N") (class "Default")
      (node (ref "P2") (pin "2") (pinfunction "2_2") (pintype "passive"))
      (node (ref "U2") (pin "18") (pinfunction "D-_18") (pintype "bidirectional"))
    )
    (net (code "41") (name "/USB_P") (class "Default")
      (node (ref "P2") (pin "3") (pinfunction "3_3") (pintype "passive"))
      (node (ref "U2") (pin "19") (pinfunction "D+_19") (pintype "bidirectional"))
    )
    (net (code "42") (name "/USB_SUSP") (class "Default")
      (node (ref "U1") (pin "20") (pinfunction "PB2_20") (pintype "bidirectional"))
      (node (ref "U2") (pin "7") (pinfunction "GP2_7") (pintype "bidirectional"))
    )
    (net (code "43") (name "/ZERO_DET") (class "Default")
      (node (ref "R16") (pin "2") (pinfunction "2_2") (pintype "passive"))
      (node (ref "U1") (pin "10") (pinfunction "PA0_10") (pintype "bidirectional"))
    )
    (net (code "44") (name "GND") (class "Default")
      (node (ref "C1") (pin "2") (pinfunction "2_2") (pintype "passive"))
      (node (ref "C10") (pin "2") (pinfunction "2_2") (pintype "passive"))
      (node (ref "C11") (pin "1") (pinfunction "C_1") (pintype "passive"))
      (node (ref "C12") (pin "2") (pinfunction "2_2") (pintype "passive"))
      (node (ref "C13") (pin "2") (pinfunction "2_2") (pintype "passive"))
      (node (ref "C14") (pin "1") (pinfunction "C_1") (pintype "passive"))
      (node (ref "C15") (pin "2") (pinfunction "2_2") (pintype "passive"))
      (node (ref "C16") (pin "1") (pinfunction "1_1") (pintype "passive"))
      (node (ref "C17") (pin "1") (pinfunction "1_1") (pintype "passive"))
      (node (ref "C18") (pin "2") (pinfunction "2_2") (pintype "passive"))
      (node (ref "C2") (pin "2") (pinfunction "2_2") (pintype "passive"))
      (node (ref "C20") (pin "2") (pinfunction "2_2") (pintype "passive"))
      (node (ref "C21") (pin "2") (pinfunction "2_2") (pintype "passive"))
      (node (ref "C23") (pin "2") (pinfunction "2_2") (pintype "passive"))
      (node (ref "C3") (pin "2") (pinfunction "2_2") (pintype "passive"))
      (node (ref "C4") (pin "2") (pinfunction "2_2") (pintype "passive"))
      (node (ref "C5") (pin "2") (pinfunction "2_2") (pintype "passive"))
      (node (ref "C6") (pin "2") (pinfunction "2_2") (pintype "passive"))
      (node (ref "C7") (pin "1") (pinfunction "1_1") (pintype "passive"))
      (node (ref "C8") (pin "1") (pinfunction "1_1") (pintype "passive"))
      (node (ref "C9") (pin "2") (pinfunction "2_2") (pintype "passive"))
      (node (ref "D1") (pin "4") (pinfunction "2_~_4") (pintype "passive"))
      (node (ref "D2") (pin "1") (pinfunction "C_1") (pintype "passive"))
      (node (ref "J5") (pin "2") (pinfunction "2_2") (pintype "passive"))
      (node (ref "J6") (pin "2") (pinfunction "2_2") (pintype "passive"))
      (node (ref "P2") (pin "4") (pinfunction "4_4") (pintype "passive"))
      (node (ref "P2") (pin "5") (pinfunction "5_5") (pintype "passive"))
      (node (ref "P3") (pin "3") (pinfunction "3_3") (pintype "passive"))
      (node (ref "P3") (pin "5") (pinfunction "5_5") (pintype "passive"))
      (node (ref "P3") (pin "7") (pinfunction "7_7") (pintype "passive"))
      (node (ref "P3") (pin "9") (pinfunction "9_9") (pintype "passive"))
      (node (ref "P4") (pin "4") (pinfunction "4_4") (pintype "passive"))
      (node (ref "P5") (pin "4") (pinfunction "4_4") (pintype "passive"))
      (node (ref "Q2") (pin "2") (pinfunction "C_2") (pintype "passive"))
      (node (ref "Q3") (pin "2") (pinfunction "C_2") (pintype "passive"))
      (node (ref "R13") (pin "2") (pinfunction "2_2") (pintype "passive"))
      (node (ref "R18") (pin "2") (pinfunction "2_2") (pintype "passive"))
      (node (ref "R24") (pin "1") (pinfunction "1_1") (pintype "passive"))
      (node (ref "R7") (pin "1") (pinfunction "1_1") (pintype "passive"))
      (node (ref "SW1") (pin "1") (pinfunction "1_1") (pintype "passive"))
      (node (ref "U1") (pin "23") (pinfunction "VSS_23") (pintype "power_in"))
      (node (ref "U1") (pin "47") (pinfunction "VSS_47") (pintype "power_in"))
      (node (ref "U1") (pin "8") (pinfunction "VSSA_8") (pintype "power_in"))
      (node (ref "U2") (pin "20") (pinfunction "VSS_20") (pintype "power_in"))
      (node (ref "U3") (pin "1") (pinfunction "GND_1") (pintype "power_in"))
      (node (ref "U4") (pin "1") (pinfunction "GND_1") (pintype "power_in"))
      (node (ref "VR1") (pin "1") (pinfunction "FIXED/ADJ_1") (pintype "input"))
    )
    (net (code "45") (name "Net-(D1-+)") (class "Default")
      (node (ref "D1") (pin "2") (pinfunction "+_2") (pintype "passive"))
      (node (ref "J1") (pin "2") (pinfunction "2_2") (pintype "passive"))
    )
    (net (code "46") (name "Net-(D1-1_~)") (class "Default")
      (node (ref "D1") (pin "1") (pinfunction "1_~_1") (pintype "passive"))
      (node (ref "J1") (pin "1") (pinfunction "1_1") (pintype "passive"))
    )
    (net (code "47") (name "Net-(D2-A)") (class "Default")
      (node (ref "D2") (pin "2") (pinfunction "A_2") (pintype "passive"))
      (node (ref "R8") (pin "1") (pinfunction "1_1") (pintype "passive"))
    )
    (net (code "48") (name "Net-(D3-G)") (class "Default")
      (node (ref "D3") (pin "3") (pinfunction "G_3") (pintype "passive"))
      (node (ref "Q3") (pin "4") (pinfunction "1_MAIN_TERM_4") (pintype "passive"))
    )
    (net (code "49") (name "Net-(D3-MT2)") (class "Default")
      (node (ref "D3") (pin "2") (pinfunction "MT2_2") (pintype "passive"))
      (node (ref "J3") (pin "1") (pinfunction "1_1") (pintype "passive"))
    )
    (net (code "50") (name "Net-(J4-Pad1)") (class "Default")
      (node (ref "J4") (pin "1") (pinfunction "1_1") (pintype "passive"))
      (node (ref "L4") (pin "1") (pinfunction "1_1") (pintype "passive"))
    )
    (net (code "51") (name "Net-(J4-Pad2)") (class "Default")
      (node (ref "J4") (pin "2") (pinfunction "2_2") (pintype "passive"))
      (node (ref "L3") (pin "1") (pinfunction "1_1") (pintype "passive"))
    )
    (net (code "52") (name "Net-(Q1-B)") (class "Default")
      (node (ref "Q1") (pin "1") (pinfunction "B_1") (pintype "passive"))
      (node (ref "R3") (pin "1") (pinfunction "1_1") (pintype "passive"))
    )
    (net (code "53") (name "Net-(Q1-E)") (class "Default")
      (node (ref "Q1") (pin "2") (pinfunction "E_2") (pintype "passive"))
      (node (ref "R8") (pin "2") (pinfunction "2_2") (pintype "passive"))
    )
    (net (code "54") (name "Net-(Q2-A)") (class "Default")
      (node (ref "Q2") (pin "1") (pinfunction "A_1") (pintype "passive"))
      (node (ref "R14") (pin "1") (pinfunction "1_1") (pintype "passive"))
    )
    (net (code "55") (name "Net-(Q2-E)") (class "Default")
      (node (ref "Q2") (pin "3") (pinfunction "E_3") (pintype "passive"))
      (node (ref "R16") (pin "1") (pinfunction "1_1") (pintype "passive"))
      (node (ref "R18") (pin "1") (pinfunction "1_1") (pintype "passive"))
    )
    (net (code "56") (name "Net-(Q3-2_MAIN_TERM)") (class "Default")
      (node (ref "Q3") (pin "6") (pinfunction "2_MAIN_TERM_6") (pintype "passive"))
      (node (ref "R20") (pin "2") (pinfunction "2_2") (pintype "passive"))
    )
    (net (code "57") (name "Net-(Q3-A)") (class "Default")
      (node (ref "Q3") (pin "1") (pinfunction "A_1") (pintype "passive"))
      (node (ref "R19") (pin "1") (pinfunction "1_1") (pintype "passive"))
    )
    (net (code "58") (name "Net-(Q4-B)") (class "Default")
      (node (ref "Q4") (pin "1") (pinfunction "B_1") (pintype "passive"))
      (node (ref "R26") (pin "1") (pinfunction "1_1") (pintype "passive"))
    )
    (net (code "59") (name "Net-(Q4-E)") (class "Default")
      (node (ref "Q4") (pin "2") (pinfunction "E_2") (pintype "passive"))
      (node (ref "Q5") (pin "1") (pinfunction "B_1") (pintype "passive"))
    )
    (net (code "60") (name "Net-(Q5-E)") (class "Default")
      (node (ref "J5") (pin "1") (pinfunction "1_1") (pintype "passive"))
      (node (ref "Q5") (pin "3") (pinfunction "E_3") (pintype "passive"))
    )
    (net (code "61") (name "Net-(Q6-B)") (class "Default")
      (node (ref "Q6") (pin "1") (pinfunction "B_1") (pintype "passive"))
      (node (ref "R27") (pin "1") (pinfunction "1_1") (pintype "passive"))
    )
    (net (code "62") (name "Net-(Q6-E)") (class "Default")
      (node (ref "Q6") (pin "2") (pinfunction "E_2") (pintype "passive"))
      (node (ref "Q7") (pin "1") (pinfunction "B_1") (pintype "passive"))
    )
    (net (code "63") (name "Net-(Q7-E)") (class "Default")
      (node (ref "J6") (pin "1") (pinfunction "1_1") (pintype "passive"))
      (node (ref "Q7") (pin "3") (pinfunction "E_3") (pintype "passive"))
    )
    (net (code "64") (name "Net-(U1A-BOOT0)") (class "Default")
      (node (ref "R13") (pin "1") (pinfunction "1_1") (pintype "passive"))
      (node (ref "U1") (pin "44") (pinfunction "BOOT0_44") (pintype "input"))
    )
    (net (code "65") (name "Net-(U1A-NRST)") (class "Default")
      (node (ref "C18") (pin "1") (pinfunction "1_1") (pintype "passive"))
      (node (ref "R15") (pin "1") (pinfunction "1_1") (pintype "passive"))
      (node (ref "R17") (pin "1") (pinfunction "1_1") (pintype "passive"))
      (node (ref "U1") (pin "7") (pinfunction "NRST_7") (pintype "bidirectional"))
    )
    (net (code "66") (name "Net-(U1A-PF0-OSC_IN(PF0))") (class "Default")
      (node (ref "C16") (pin "2") (pinfunction "2_2") (pintype "passive"))
      (node (ref "U1") (pin "5") (pinfunction "PF0-OSC_IN(PF0)_5") (pintype "bidirectional"))
      (node (ref "Y2") (pin "2") (pinfunction "2_2") (pintype "passive"))
    )
    (net (code "67") (name "Net-(U1A-PF1-OSC_OUT(PF1))") (class "Default")
      (node (ref "C17") (pin "2") (pinfunction "2_2") (pintype "passive"))
      (node (ref "U1") (pin "6") (pinfunction "PF1-OSC_OUT(PF1)_6") (pintype "bidirectional"))
      (node (ref "Y2") (pin "1") (pinfunction "1_1") (pintype "passive"))
    )
    (net (code "68") (name "Net-(U2-GP3)") (class "Default")
      (node (ref "R3") (pin "2") (pinfunction "2_2") (pintype "passive"))
      (node (ref "U2") (pin "8") (pinfunction "GP3_8") (pintype "bidirectional"))
    )
    (net (code "69") (name "Net-(U2-OSC1)") (class "Default")
      (node (ref "C7") (pin "2") (pinfunction "2_2") (pintype "passive"))
      (node (ref "U2") (pin "2") (pinfunction "OSC1_2") (pintype "input"))
      (node (ref "Y1") (pin "2") (pinfunction "2_2") (pintype "passive"))
    )
    (net (code "70") (name "Net-(U2-OSC2)") (class "Default")
      (node (ref "C8") (pin "2") (pinfunction "2_2") (pintype "passive"))
      (node (ref "U2") (pin "3") (pinfunction "OSC2_3") (pintype "output"))
      (node (ref "Y1") (pin "1") (pinfunction "1_1") (pintype "passive"))
    )
    (net (code "71") (name "Net-(U2-~{RST})") (class "Default")
      (node (ref "R2") (pin "2") (pinfunction "2_2") (pintype "passive"))
      (node (ref "U2") (pin "4") (pinfunction "~{RST}_4") (pintype "input"))
    )
    (net (code "72") (name "Net-(U3-T+)") (class "Default")
      (node (ref "C19") (pin "1") (pinfunction "1_1") (pintype "passive"))
      (node (ref "L1") (pin "2") (pinfunction "2_2") (pintype "passive"))
      (node (ref "U3") (pin "3") (pinfunction "T+_3") (pintype "input"))
    )
    (net (code "73") (name "Net-(U3-T-)") (class "Default")
      (node (ref "C19") (pin "2") (pinfunction "2_2") (pintype "passive"))
      (node (ref "L2") (pin "2") (pinfunction "2_2") (pintype "passive"))
      (node (ref "U3") (pin "2") (pinfunction "T-_2") (pintype "input"))
    )
    (net (code "74") (name "Net-(U4-T+)") (class "Default")
      (node (ref "C22") (pin "1") (pinfunction "1_1") (pintype "passive"))
      (node (ref "L3") (pin "2") (pinfunction "2_2") (pintype "passive"))
      (node (ref "U4") (pin "3") (pinfunction "T+_3") (pintype "input"))
    )
    (net (code "75") (name "Net-(U4-T-)") (class "Default")
      (node (ref "C22") (pin "2") (pinfunction "2_2") (pintype "passive"))
      (node (ref "L4") (pin "2") (pinfunction "2_2") (pintype "passive"))
      (node (ref "U4") (pin "2") (pinfunction "T-_2") (pintype "input"))
    )
    (net (code "76") (name "unconnected-(J1-Pad3)") (class "Default")
      (node (ref "J1") (pin "3") (pinfunction "3_3") (pintype "passive+no_connect"))
    )
    (net (code "77") (name "unconnected-(J1-Pad4)") (class "Default")
      (node (ref "J1") (pin "4") (pinfunction "4_4") (pintype "passive+no_connect"))
    )
    (net (code "78") (name "unconnected-(J1-Pad5)") (class "Default")
      (node (ref "J1") (pin "5") (pinfunction "5_5") (pintype "passive+no_connect"))
    )
    (net (code "79") (name "unconnected-(P2-Pad1)") (class "Default")
      (node (ref "P2") (pin "1") (pinfunction "1_1") (pintype "passive+no_connect"))
    )
    (net (code "80") (name "unconnected-(P3-Pad6)") (class "Default")
      (node (ref "P3") (pin "6") (pinfunction "6_6") (pintype "passive"))
    )
    (net (code "81") (name "unconnected-(P3-Pad8)") (class "Default")
      (node (ref "P3") (pin "8") (pinfunction "8_8") (pintype "passive"))
    )
    (net (code "82") (name "unconnected-(Q3-NC-Pad3)") (class "Default")
      (node (ref "Q3") (pin "3") (pinfunction "NC_3") (pintype "passive+no_connect"))
    )
    (net (code "83") (name "unconnected-(Q3-NC-Pad5)") (class "Default")
      (node (ref "Q3") (pin "5") (pinfunction "NC_5") (pintype "passive+no_connect"))
    )
    (net (code "84") (name "unconnected-(U1A-PA3-Pad13)") (class "Default")
      (node (ref "U1") (pin "13") (pinfunction "PA3_13") (pintype "bidirectional"))
    )
    (net (code "85") (name "unconnected-(U1A-PA7-Pad17)") (class "Default")
      (node (ref "U1") (pin "17") (pinfunction "PA7_17") (pintype "bidirectional"))
    )
    (net (code "86") (name "unconnected-(U1A-PA8-Pad29)") (class "Default")
      (node (ref "U1") (pin "29") (pinfunction "PA8_29") (pintype "bidirectional"))
    )
    (net (code "87") (name "unconnected-(U1A-PA11-Pad32)") (class "Default")
      (node (ref "U1") (pin "32") (pinfunction "PA11_32") (pintype "bidirectional"))
    )
    (net (code "88") (name "unconnected-(U1A-PA12-Pad33)") (class "Default")
      (node (ref "U1") (pin "33") (pinfunction "PA12_33") (pintype "bidirectional"))
    )
    (net (code "89") (name "unconnected-(U1A-PC13-Pad2)") (class "Default")
      (node (ref "U1") (pin "2") (pinfunction "PC13_2") (pintype "bidirectional"))
    )
    (net (code "90") (name "unconnected-(U1A-PC14-OSC32_IN(PC14)-Pad3)") (class "Default")
      (node (ref "U1") (pin "3") (pinfunction "PC14-OSC32_IN(PC14)_3") (pintype "bidirectional"))
    )
    (net (code "91") (name "unconnected-(U1A-PC15-OSC32_OUT(PC15)-Pad4)") (class "Default")
      (node (ref "U1") (pin "4") (pinfunction "PC15-OSC32_OUT(PC15)_4") (pintype "bidirectional"))
    )
    (net (code "92") (name "unconnected-(U1A-PF6-Pad35)") (class "Default")
      (node (ref "U1") (pin "35") (pinfunction "PF6_35") (pintype "bidirectional"))
    )
    (net (code "93") (name "unconnected-(U1A-PF7-Pad36)") (class "Default")
      (node (ref "U1") (pin "36") (pinfunction "PF7_36") (pintype "bidirectional"))
    )
    (net (code "94") (name "unconnected-(U2-GP1-Pad6)") (class "Default")
      (node (ref "U2") (pin "6") (pinfunction "GP1_6") (pintype "bidirectional"))
    )
    (net (code "95") (name "unconnected-(U3-DNC-Pad8)") (class "Default")
      (node (ref "U3") (pin "8") (pinfunction "DNC_8") (pintype "passive"))
    )
    (net (code "96") (name "unconnected-(U4-DNC-Pad8)") (class "Default")
      (node (ref "U4") (pin "8") (pinfunction "DNC_8") (pintype "passive"))
    )
    (net (code "97") (name "~230") (class "Default")
      (node (ref "D3") (pin "1") (pinfunction "MT1_1") (pintype "passive"))
      (node (ref "J2") (pin "1") (pinfunction "1_1") (pintype "passive"))
      (node (ref "J2") (pin "2") (pinfunction "2_2") (pintype "passive"))
      (node (ref "R20") (pin "1") (pinfunction "1_1") (pintype "passive"))
      (node (ref "R28") (pin "2") (pinfunction "2_2") (pintype "passive"))
    )
    (net (code "98") (name "~N") (class "Default")
      (node (ref "J2") (pin "3") (pinfunction "3_3") (pintype "passive"))
      (node (ref "J2") (pin "4") (pinfunction "4_4") (pintype "passive"))
      (node (ref "J3") (pin "2") (pinfunction "2_2") (pintype "passive"))
      (node (ref "R28") (pin "1") (pinfunction "1_1") (pintype "passive"))
    )
  )
)
